# sensor.net
KiCad netlist of a schematic drawn in EAGLE
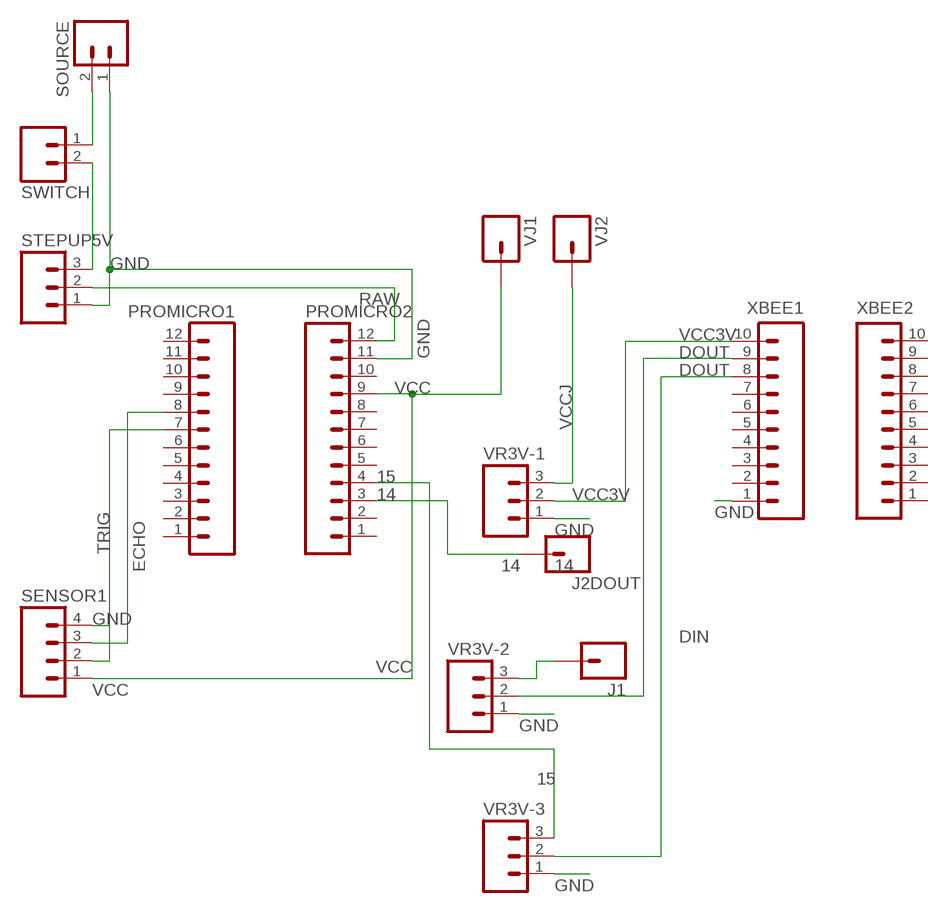
[diagram p0: schematic, sheet 1]

(export (version "E")
  (design (tool "Eeschema 10.0.6"))
  (components
    (comp (ref "J1")
      (value "M01PTH")
      (footprint "eagle-import:1X01")
      (libsource (lib "eagle-import") (part "M01PTH"))
    )
    (comp (ref "J2")
      (value "M01PTH")
      (footprint "eagle-import:1X01")
      (libsource (lib "eagle-import") (part "M01PTH"))
    )
    (comp (ref "PROMICRO1")
      (value "M12LOCK")
      (footprint "eagle-import:1X12_LOCK")
      (libsource (lib "eagle-import") (part "M12LOCK"))
    )
    (comp (ref "PROMICRO2")
      (value "M12LOCK")
      (footprint "eagle-import:1X12_LOCK")
      (libsource (lib "eagle-import") (part "M12LOCK"))
    )
    (comp (ref "SENSOR1")
      (value "M04LOCK")
      (footprint "eagle-import:1X04_LOCK")
      (libsource (lib "eagle-import") (part "M04LOCK"))
    )
    (comp (ref "SOURCE")
      (value "M02JST-PTH-VERT")
      (footprint "eagle-import:JST-2-PTH-VERT")
      (libsource (lib "eagle-import") (part "M02JST-PTH-VERT"))
    )
    (comp (ref "STEPUP5V")
      (value "M03PTH")
      (footprint "eagle-import:1X03")
      (libsource (lib "eagle-import") (part "M03PTH"))
    )
    (comp (ref "SWITCH")
      (value "M02PTH")
      (footprint "eagle-import:1X02")
      (libsource (lib "eagle-import") (part "M02PTH"))
    )
    (comp (ref "VJ1")
      (value "M01PTH")
      (footprint "eagle-import:1X01")
      (libsource (lib "eagle-import") (part "M01PTH"))
    )
    (comp (ref "VJ2")
      (value "M01PTH")
      (footprint "eagle-import:1X01")
      (libsource (lib "eagle-import") (part "M01PTH"))
    )
    (comp (ref "VR3V-1")
      (value "M03PTH")
      (footprint "eagle-import:1X03")
      (libsource (lib "eagle-import") (part "M03PTH"))
    )
    (comp (ref "VR3V-2")
      (value "M03PTH")
      (footprint "eagle-import:1X03")
      (libsource (lib "eagle-import") (part "M03PTH"))
    )
    (comp (ref "VR3V-3")
      (value "M03PTH")
      (footprint "eagle-import:1X03")
      (libsource (lib "eagle-import") (part "M03PTH"))
    )
    (comp (ref "XBEE1")
      (value "M10LOCK")
      (footprint "eagle-import:1X10_LOCK")
      (libsource (lib "eagle-import") (part "M10LOCK"))
    )
    (comp (ref "XBEE2")
      (value "M10LOCK")
      (footprint "eagle-import:1X10_LOCK")
      (libsource (lib "eagle-import") (part "M10LOCK"))
    )
  )
  (nets
    (net (code "1") (name "/14") (class "Default")
      (node (ref "J2") (pin "1") (pinfunction "1_1") (pintype "passive"))
      (node (ref "PROMICRO2") (pin "3") (pinfunction "3_3") (pintype "passive"))
    )
    (net (code "2") (name "/15") (class "Default")
      (node (ref "PROMICRO2") (pin "4") (pinfunction "4_4") (pintype "passive"))
      (node (ref "VR3V-3") (pin "3") (pinfunction "3_3") (pintype "passive"))
    )
    (net (code "3") (name "/DIN") (class "Default")
      (node (ref "VR3V-3") (pin "2") (pinfunction "2_2") (pintype "passive"))
      (node (ref "XBEE1") (pin "8") (pinfunction "8_8") (pintype "passive"))
    )
    (net (code "4") (name "/DOUT") (class "Default")
      (node (ref "VR3V-2") (pin "2") (pinfunction "2_2") (pintype "passive"))
      (node (ref "XBEE1") (pin "9") (pinfunction "9_9") (pintype "passive"))
    )
    (net (code "5") (name "/ECHO") (class "Default")
      (node (ref "PROMICRO1") (pin "8") (pinfunction "8_8") (pintype "passive"))
      (node (ref "SENSOR1") (pin "3") (pinfunction "3_3") (pintype "passive"))
    )
    (net (code "6") (name "/GND") (class "Default")
      (node (ref "PROMICRO2") (pin "11") (pinfunction "11_11") (pintype "passive"))
      (node (ref "SENSOR1") (pin "4") (pinfunction "4_4") (pintype "passive"))
      (node (ref "SOURCE") (pin "1") (pinfunction "1_1") (pintype "passive"))
      (node (ref "STEPUP5V") (pin "1") (pinfunction "1_1") (pintype "passive"))
      (node (ref "VR3V-1") (pin "1") (pinfunction "1_1") (pintype "passive"))
      (node (ref "VR3V-2") (pin "1") (pinfunction "1_1") (pintype "passive"))
      (node (ref "VR3V-3") (pin "1") (pinfunction "1_1") (pintype "passive"))
      (node (ref "XBEE1") (pin "1") (pinfunction "1_1") (pintype "passive"))
    )
    (net (code "7") (name "/RAW") (class "Default")
      (node (ref "PROMICRO2") (pin "12") (pinfunction "12_12") (pintype "passive"))
      (node (ref "STEPUP5V") (pin "2") (pinfunction "2_2") (pintype "passive"))
    )
    (net (code "8") (name "/TRIG") (class "Default")
      (node (ref "PROMICRO1") (pin "7") (pinfunction "7_7") (pintype "passive"))
      (node (ref "SENSOR1") (pin "2") (pinfunction "2_2") (pintype "passive"))
    )
    (net (code "9") (name "/VCC") (class "Default")
      (node (ref "PROMICRO2") (pin "9") (pinfunction "9_9") (pintype "passive"))
      (node (ref "SENSOR1") (pin "1") (pinfunction "1_1") (pintype "passive"))
      (node (ref "VJ1") (pin "1") (pinfunction "1_1") (pintype "passive"))
    )
    (net (code "10") (name "/VCC3V") (class "Default")
      (node (ref "VR3V-1") (pin "2") (pinfunction "2_2") (pintype "passive"))
      (node (ref "XBEE1") (pin "10") (pinfunction "10_10") (pintype "passive"))
    )
    (net (code "11") (name "/VCCJ") (class "Default")
      (node (ref "VJ2") (pin "1") (pinfunction "1_1") (pintype "passive"))
      (node (ref "VR3V-1") (pin "3") (pinfunction "3_3") (pintype "passive"))
    )
    (net (code "12") (name "Net-(J1-Pad1)") (class "Default")
      (node (ref "J1") (pin "1") (pinfunction "1_1") (pintype "passive"))
      (node (ref "VR3V-2") (pin "3") (pinfunction "3_3") (pintype "passive"))
    )
    (net (code "13") (name "Net-(SOURCE-Pad2)") (class "Default")
      (node (ref "SOURCE") (pin "2") (pinfunction "2_2") (pintype "passive"))
      (node (ref "SWITCH") (pin "1") (pinfunction "1_1") (pintype "passive"))
    )
    (net (code "14") (name "Net-(STEPUP5V-Pad3)") (class "Default")
      (node (ref "STEPUP5V") (pin "3") (pinfunction "3_3") (pintype "passive"))
      (node (ref "SWITCH") (pin "2") (pinfunction "2_2") (pintype "passive"))
    )
    (net (code "15") (name "unconnected-(PROMICRO1-Pad1)") (class "Default")
      (node (ref "PROMICRO1") (pin "1") (pinfunction "1_1") (pintype "passive"))
    )
    (net (code "16") (name "unconnected-(PROMICRO1-Pad2)") (class "Default")
      (node (ref "PROMICRO1") (pin "2") (pinfunction "2_2") (pintype "passive"))
    )
    (net (code "17") (name "unconnected-(PROMICRO1-Pad3)") (class "Default")
      (node (ref "PROMICRO1") (pin "3") (pinfunction "3_3") (pintype "passive"))
    )
    (net (code "18") (name "unconnected-(PROMICRO1-Pad4)") (class "Default")
      (node (ref "PROMICRO1") (pin "4") (pinfunction "4_4") (pintype "passive"))
    )
    (net (code "19") (name "unconnected-(PROMICRO1-Pad5)") (class "Default")
      (node (ref "PROMICRO1") (pin "5") (pinfunction "5_5") (pintype "passive"))
    )
    (net (code "20") (name "unconnected-(PROMICRO1-Pad6)") (class "Default")
      (node (ref "PROMICRO1") (pin "6") (pinfunction "6_6") (pintype "passive"))
    )
    (net (code "21") (name "unconnected-(PROMICRO1-Pad9)") (class "Default")
      (node (ref "PROMICRO1") (pin "9") (pinfunction "9_9") (pintype "passive"))
    )
    (net (code "22") (name "unconnected-(PROMICRO1-Pad10)") (class "Default")
      (node (ref "PROMICRO1") (pin "10") (pinfunction "10_10") (pintype "passive"))
    )
    (net (code "23") (name "unconnected-(PROMICRO1-Pad11)") (class "Default")
      (node (ref "PROMICRO1") (pin "11") (pinfunction "11_11") (pintype "passive"))
    )
    (net (code "24") (name "unconnected-(PROMICRO1-Pad12)") (class "Default")
      (node (ref "PROMICRO1") (pin "12") (pinfunction "12_12") (pintype "passive"))
    )
    (net (code "25") (name "unconnected-(PROMICRO2-Pad1)") (class "Default")
      (node (ref "PROMICRO2") (pin "1") (pinfunction "1_1") (pintype "passive"))
    )
    (net (code "26") (name "unconnected-(PROMICRO2-Pad2)") (class "Default")
      (node (ref "PROMICRO2") (pin "2") (pinfunction "2_2") (pintype "passive"))
    )
    (net (code "27") (name "unconnected-(PROMICRO2-Pad5)") (class "Default")
      (node (ref "PROMICRO2") (pin "5") (pinfunction "5_5") (pintype "passive"))
    )
    (net (code "28") (name "unconnected-(PROMICRO2-Pad6)") (class "Default")
      (node (ref "PROMICRO2") (pin "6") (pinfunction "6_6") (pintype "passive"))
    )
    (net (code "29") (name "unconnected-(PROMICRO2-Pad7)") (class "Default")
      (node (ref "PROMICRO2") (pin "7") (pinfunction "7_7") (pintype "passive"))
    )
    (net (code "30") (name "unconnected-(PROMICRO2-Pad8)") (class "Default")
      (node (ref "PROMICRO2") (pin "8") (pinfunction "8_8") (pintype "passive"))
    )
    (net (code "31") (name "unconnected-(PROMICRO2-Pad10)") (class "Default")
      (node (ref "PROMICRO2") (pin "10") (pinfunction "10_10") (pintype "passive"))
    )
    (net (code "32") (name "unconnected-(XBEE1-Pad2)") (class "Default")
      (node (ref "XBEE1") (pin "2") (pinfunction "2_2") (pintype "passive"))
    )
    (net (code "33") (name "unconnected-(XBEE1-Pad3)") (class "Default")
      (node (ref "XBEE1") (pin "3") (pinfunction "3_3") (pintype "passive"))
    )
    (net (code "34") (name "unconnected-(XBEE1-Pad4)") (class "Default")
      (node (ref "XBEE1") (pin "4") (pinfunction "4_4") (pintype "passive"))
    )
    (net (code "35") (name "unconnected-(XBEE1-Pad5)") (class "Default")
      (node (ref "XBEE1") (pin "5") (pinfunction "5_5") (pintype "passive"))
    )
    (net (code "36") (name "unconnected-(XBEE1-Pad6)") (class "Default")
      (node (ref "XBEE1") (pin "6") (pinfunction "6_6") (pintype "passive"))
    )
    (net (code "37") (name "unconnected-(XBEE1-Pad7)") (class "Default")
      (node (ref "XBEE1") (pin "7") (pinfunction "7_7") (pintype "passive"))
    )
    (net (code "38") (name "unconnected-(XBEE2-Pad1)") (class "Default")
      (node (ref "XBEE2") (pin "1") (pinfunction "1_1") (pintype "passive"))
    )
    (net (code "39") (name "unconnected-(XBEE2-Pad2)") (class "Default")
      (node (ref "XBEE2") (pin "2") (pinfunction "2_2") (pintype "passive"))
    )
    (net (code "40") (name "unconnected-(XBEE2-Pad3)") (class "Default")
      (node (ref "XBEE2") (pin "3") (pinfunction "3_3") (pintype "passive"))
    )
    (net (code "41") (name "unconnected-(XBEE2-Pad4)") (class "Default")
      (node (ref "XBEE2") (pin "4") (pinfunction "4_4") (pintype "passive"))
    )
    (net (code "42") (name "unconnected-(XBEE2-Pad5)") (class "Default")
      (node (ref "XBEE2") (pin "5") (pinfunction "5_5") (pintype "passive"))
    )
    (net (code "43") (name "unconnected-(XBEE2-Pad6)") (class "Default")
      (node (ref "XBEE2") (pin "6") (pinfunction "6_6") (pintype "passive"))
    )
    (net (code "44") (name "unconnected-(XBEE2-Pad7)") (class "Default")
      (node (ref "XBEE2") (pin "7") (pinfunction "7_7") (pintype "passive"))
    )
    (net (code "45") (name "unconnected-(XBEE2-Pad8)") (class "Default")
      (node (ref "XBEE2") (pin "8") (pinfunction "8_8") (pintype "passive"))
    )
    (net (code "46") (name "unconnected-(XBEE2-Pad9)") (class "Default")
      (node (ref "XBEE2") (pin "9") (pinfunction "9_9") (pintype "passive"))
    )
    (net (code "47") (name "unconnected-(XBEE2-Pad10)") (class "Default")
      (node (ref "XBEE2") (pin "10") (pinfunction "10_10") (pintype "passive"))
    )
  )
)
